# host-Insulation.net
KiCad netlist of a schematic drawn in EAGLE
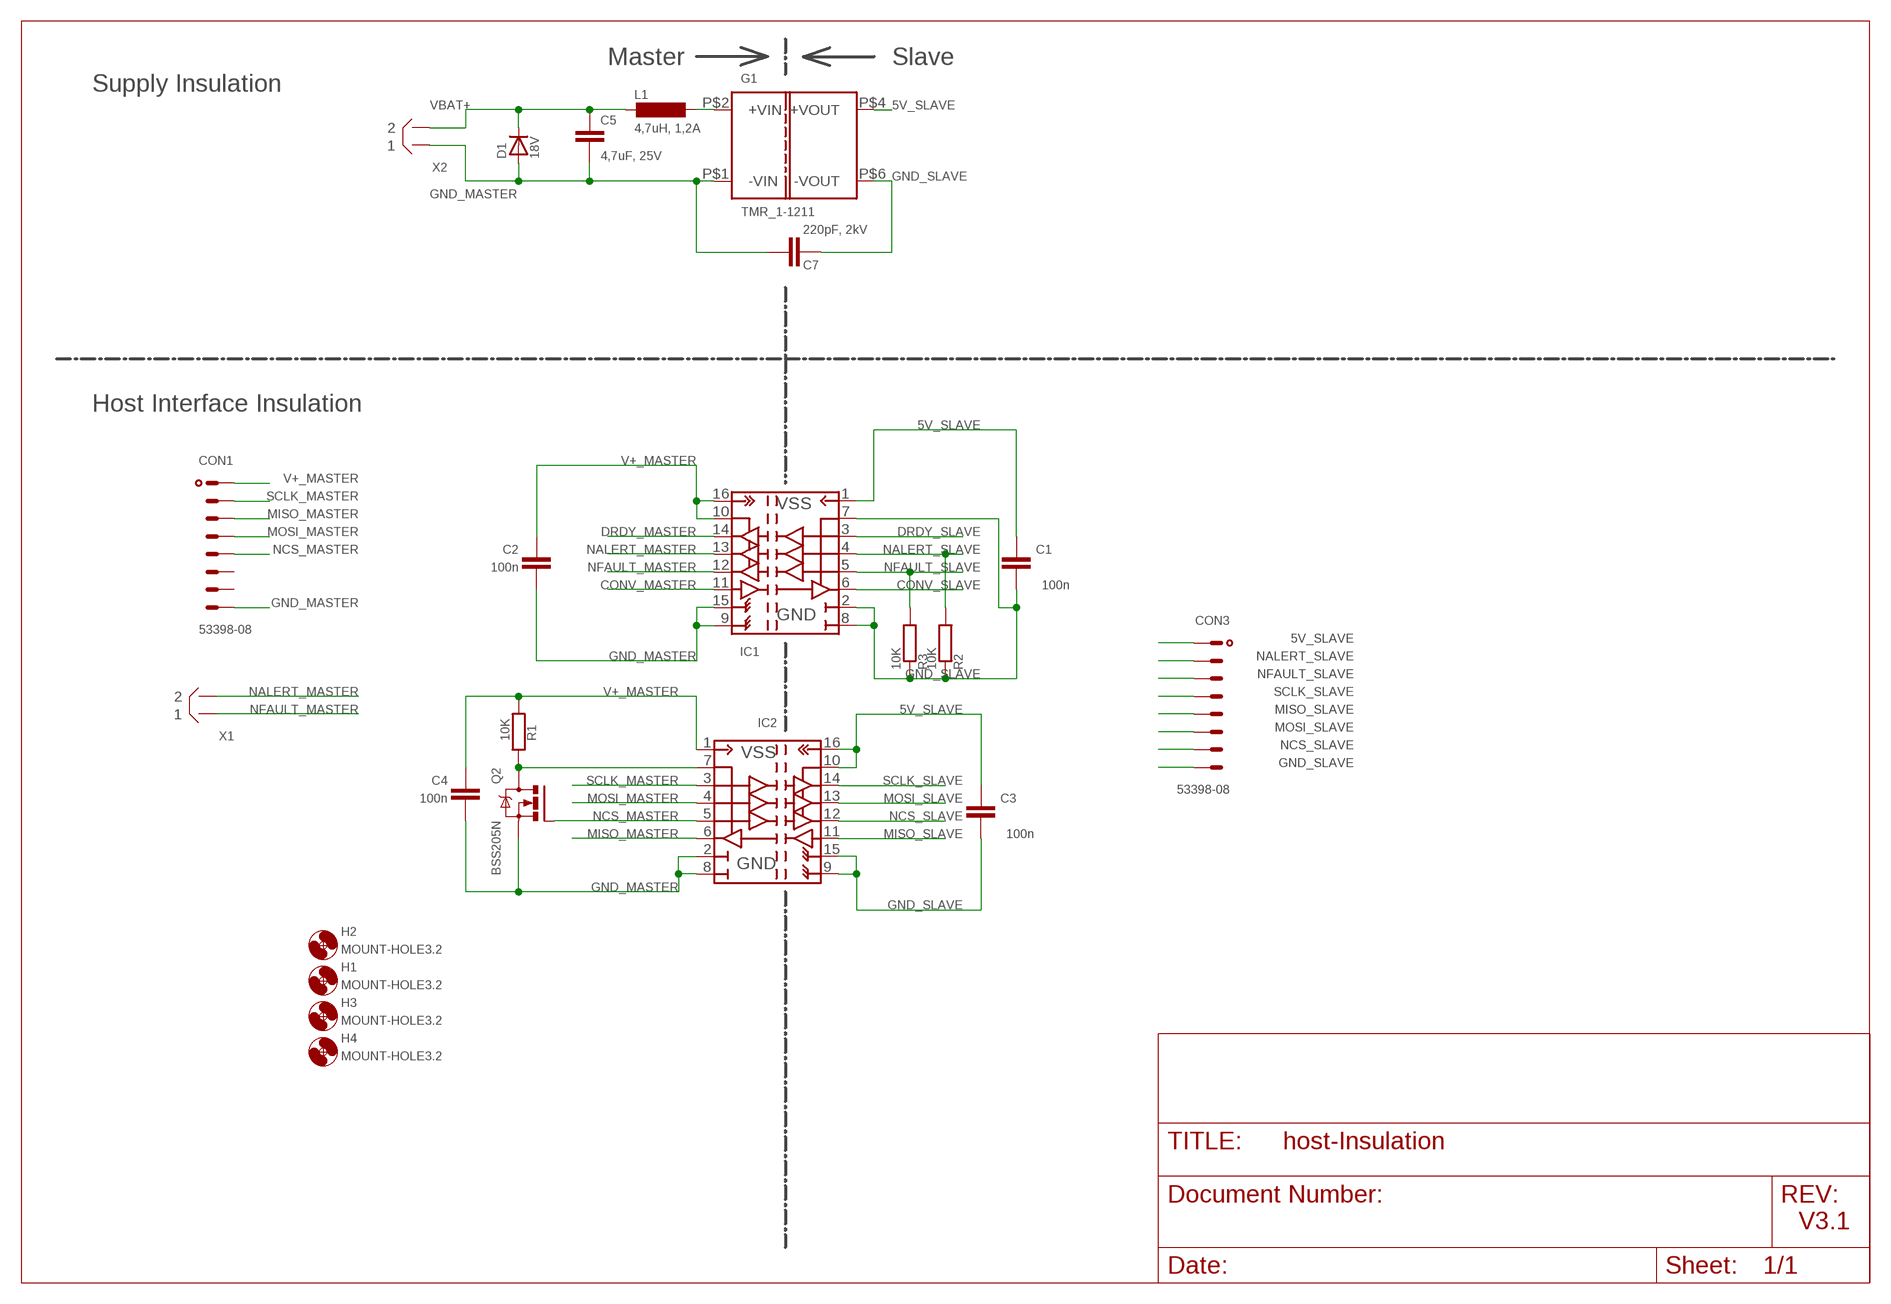
[diagram p0: schematic, sheet 1]

(export (version "E")
  (design (tool "Eeschema 10.0.6"))
  (components
    (comp (ref "C1")
      (value "100n")
      (footprint "eagle-import:C0805")
      (libsource (lib "eagle-import") (part "CSTD"))
    )
    (comp (ref "C2")
      (value "100n")
      (footprint "eagle-import:C0805")
      (libsource (lib "eagle-import") (part "CSTD"))
    )
    (comp (ref "C3")
      (value "100n")
      (footprint "eagle-import:C0805")
      (libsource (lib "eagle-import") (part "CSTD"))
    )
    (comp (ref "C4")
      (value "100n")
      (footprint "eagle-import:C0805")
      (libsource (lib "eagle-import") (part "CSTD"))
    )
    (comp (ref "C5")
      (value "4,7uF, 25V")
      (footprint "eagle-import:C0805")
      (libsource (lib "eagle-import") (part "C-EUC0805"))
    )
    (comp (ref "C7")
      (value "220pF, 2kV")
      (footprint "eagle-import:C1210_HV")
      (libsource (lib "eagle-import") (part "CC1210_HV"))
    )
    (comp (ref "CON1")
      (value "53398-08")
      (footprint "eagle-import:53398-08")
      (libsource (lib "eagle-import") (part "53?-08398"))
    )
    (comp (ref "CON3")
      (value "53398-08")
      (footprint "eagle-import:53398-08")
      (libsource (lib "eagle-import") (part "53?-08398"))
    )
    (comp (ref "D1")
      (value "18V")
      (footprint "eagle-import:DO214AA")
      (libsource (lib "eagle-import") (part "DIODE-DO214AA"))
    )
    (comp (ref "G1")
      (value "TMR_1-1211")
      (footprint "eagle-import:TMR_1-__1_")
      (libsource (lib "eagle-import") (part "TMR_1-??1?"))
    )
    (comp (ref "H1")
      (value "MOUNT-HOLE3.2")
      (footprint "eagle-import:3,2")
      (libsource (lib "eagle-import") (part "MOUNT-HOLE3.2"))
    )
    (comp (ref "H2")
      (value "MOUNT-HOLE3.2")
      (footprint "eagle-import:3,2")
      (libsource (lib "eagle-import") (part "MOUNT-HOLE3.2"))
    )
    (comp (ref "H3")
      (value "MOUNT-HOLE3.2")
      (footprint "eagle-import:3,2")
      (libsource (lib "eagle-import") (part "MOUNT-HOLE3.2"))
    )
    (comp (ref "H4")
      (value "MOUNT-HOLE3.2")
      (footprint "eagle-import:3,2")
      (libsource (lib "eagle-import") (part "MOUNT-HOLE3.2"))
    )
    (comp (ref "IC1")
      (value "ISO7241")
      (footprint "eagle-import:R-PDSO-G16")
      (libsource (lib "eagle-import") (part "ISO7241"))
    )
    (comp (ref "IC2")
      (value "ISO7241")
      (footprint "eagle-import:R-PDSO-G16")
      (libsource (lib "eagle-import") (part "ISO7241"))
    )
    (comp (ref "L1")
      (value "4,7uH, 1,2A")
      (footprint "eagle-import:L3225M")
      (libsource (lib "eagle-import") (part "L-EUL3225M"))
    )
    (comp (ref "Q2")
      (value "BSS205N")
      (footprint "eagle-import:SOT23")
      (libsource (lib "eagle-import") (part "BSS205N"))
    )
    (comp (ref "R1")
      (value "10K")
      (footprint "eagle-import:R0805")
      (libsource (lib "eagle-import") (part "R"))
    )
    (comp (ref "R2")
      (value "10K")
      (footprint "eagle-import:R0805")
      (libsource (lib "eagle-import") (part "R"))
    )
    (comp (ref "R3")
      (value "10K")
      (footprint "eagle-import:R0805")
      (libsource (lib "eagle-import") (part "R"))
    )
    (comp (ref "X1")
      (value "B2B-XH")
      (footprint "eagle-import:B2B-XH")
      (libsource (lib "eagle-import") (part "?2B-XHB"))
    )
    (comp (ref "X2")
      (value "B2B-XH")
      (footprint "eagle-import:B2B-XH")
      (libsource (lib "eagle-import") (part "?2B-XHB"))
    )
  )
  (nets
    (net (code "1") (name "/5V_SLAVE") (class "Default")
      (node (ref "C1") (pin "2") (pinfunction "2_2") (pintype "passive"))
      (node (ref "C3") (pin "2") (pinfunction "2_2") (pintype "passive"))
      (node (ref "CON3") (pin "1") (pinfunction "1_1") (pintype "passive"))
      (node (ref "G1") (pin "P$4") (pinfunction "+VOUT_P$4") (pintype "bidirectional"))
      (node (ref "IC1") (pin "1") (pinfunction "VCC1_1") (pintype "bidirectional"))
      (node (ref "IC2") (pin "10") (pinfunction "EN2_10") (pintype "bidirectional"))
      (node (ref "IC2") (pin "16") (pinfunction "VCC2_16") (pintype "bidirectional"))
    )
    (net (code "2") (name "/CONV_MASTER") (class "Default")
      (node (ref "IC1") (pin "11") (pinfunction "IN_D_11") (pintype "bidirectional"))
    )
    (net (code "3") (name "/CONV_SLAVE") (class "Default")
      (node (ref "IC1") (pin "6") (pinfunction "OUT_D_6") (pintype "bidirectional"))
    )
    (net (code "4") (name "/DRDY_MASTER") (class "Default")
      (node (ref "IC1") (pin "14") (pinfunction "OUT_A_14") (pintype "bidirectional"))
    )
    (net (code "5") (name "/DRDY_SLAVE") (class "Default")
      (node (ref "IC1") (pin "3") (pinfunction "IN_A_3") (pintype "bidirectional"))
    )
    (net (code "6") (name "/GND_MASTER") (class "Default")
      (node (ref "C2") (pin "1") (pinfunction "1_1") (pintype "passive"))
      (node (ref "C4") (pin "1") (pinfunction "1_1") (pintype "passive"))
      (node (ref "C5") (pin "2") (pinfunction "2_2") (pintype "passive"))
      (node (ref "C7") (pin "P$1") (pinfunction "1_P$1") (pintype "passive"))
      (node (ref "CON1") (pin "8") (pinfunction "8_8") (pintype "passive"))
      (node (ref "D1") (pin "A") (pinfunction "A_A") (pintype "passive"))
      (node (ref "G1") (pin "P$1") (pinfunction "-VIN_P$1") (pintype "bidirectional"))
      (node (ref "IC1") (pin "15") (pinfunction "GND21_15") (pintype "bidirectional"))
      (node (ref "IC1") (pin "9") (pinfunction "GND22_9") (pintype "bidirectional"))
      (node (ref "IC2") (pin "2") (pinfunction "GND11_2") (pintype "bidirectional"))
      (node (ref "IC2") (pin "8") (pinfunction "GND12_8") (pintype "bidirectional"))
      (node (ref "Q2") (pin "2") (pinfunction "S_2") (pintype "passive"))
      (node (ref "X2") (pin "P$1") (pinfunction "1_P$1") (pintype "bidirectional"))
    )
    (net (code "7") (name "/GND_SLAVE") (class "Default")
      (node (ref "C1") (pin "1") (pinfunction "1_1") (pintype "passive"))
      (node (ref "C3") (pin "1") (pinfunction "1_1") (pintype "passive"))
      (node (ref "C7") (pin "P$2") (pinfunction "2_P$2") (pintype "passive"))
      (node (ref "CON3") (pin "8") (pinfunction "8_8") (pintype "passive"))
      (node (ref "G1") (pin "P$6") (pinfunction "-VOUT_P$6") (pintype "bidirectional"))
      (node (ref "IC1") (pin "2") (pinfunction "GND11_2") (pintype "bidirectional"))
      (node (ref "IC1") (pin "7") (pinfunction "EN1_7") (pintype "bidirectional"))
      (node (ref "IC1") (pin "8") (pinfunction "GND12_8") (pintype "bidirectional"))
      (node (ref "IC2") (pin "15") (pinfunction "GND21_15") (pintype "bidirectional"))
      (node (ref "IC2") (pin "9") (pinfunction "GND22_9") (pintype "bidirectional"))
      (node (ref "R2") (pin "1") (pinfunction "1_1") (pintype "passive"))
      (node (ref "R3") (pin "1") (pinfunction "1_1") (pintype "passive"))
    )
    (net (code "8") (name "/MISO_MASTER") (class "Default")
      (node (ref "CON1") (pin "3") (pinfunction "3_3") (pintype "passive"))
      (node (ref "IC2") (pin "6") (pinfunction "OUT_D_6") (pintype "bidirectional"))
    )
    (net (code "9") (name "/MISO_SLAVE") (class "Default")
      (node (ref "CON3") (pin "5") (pinfunction "5_5") (pintype "passive"))
      (node (ref "IC2") (pin "11") (pinfunction "IN_D_11") (pintype "bidirectional"))
    )
    (net (code "10") (name "/MOSI_MASTER") (class "Default")
      (node (ref "CON1") (pin "4") (pinfunction "4_4") (pintype "passive"))
      (node (ref "IC2") (pin "4") (pinfunction "IN_B_4") (pintype "bidirectional"))
    )
    (net (code "11") (name "/MOSI_SLAVE") (class "Default")
      (node (ref "CON3") (pin "6") (pinfunction "6_6") (pintype "passive"))
      (node (ref "IC2") (pin "13") (pinfunction "OUT_B_13") (pintype "bidirectional"))
    )
    (net (code "12") (name "/NALERT_MASTER") (class "Default")
      (node (ref "IC1") (pin "13") (pinfunction "OUT_B_13") (pintype "bidirectional"))
      (node (ref "X1") (pin "P$2") (pinfunction "2_P$2") (pintype "bidirectional"))
    )
    (net (code "13") (name "/NALERT_SLAVE") (class "Default")
      (node (ref "CON3") (pin "2") (pinfunction "2_2") (pintype "passive"))
      (node (ref "IC1") (pin "4") (pinfunction "IN_B_4") (pintype "bidirectional"))
      (node (ref "R2") (pin "2") (pinfunction "2_2") (pintype "passive"))
    )
    (net (code "14") (name "/NCS_MASTER") (class "Default")
      (node (ref "CON1") (pin "5") (pinfunction "5_5") (pintype "passive"))
      (node (ref "IC2") (pin "5") (pinfunction "IN_C_5") (pintype "bidirectional"))
      (node (ref "Q2") (pin "1") (pinfunction "G_1") (pintype "passive"))
    )
    (net (code "15") (name "/NCS_SLAVE") (class "Default")
      (node (ref "CON3") (pin "7") (pinfunction "7_7") (pintype "passive"))
      (node (ref "IC2") (pin "12") (pinfunction "OUT_C_12") (pintype "bidirectional"))
    )
    (net (code "16") (name "/NFAULT_MASTER") (class "Default")
      (node (ref "IC1") (pin "12") (pinfunction "OUT_C_12") (pintype "bidirectional"))
      (node (ref "X1") (pin "P$1") (pinfunction "1_P$1") (pintype "bidirectional"))
    )
    (net (code "17") (name "/NFAULT_SLAVE") (class "Default")
      (node (ref "CON3") (pin "3") (pinfunction "3_3") (pintype "passive"))
      (node (ref "IC1") (pin "5") (pinfunction "IN_C_5") (pintype "bidirectional"))
      (node (ref "R3") (pin "2") (pinfunction "2_2") (pintype "passive"))
    )
    (net (code "18") (name "/SCLK_MASTER") (class "Default")
      (node (ref "CON1") (pin "2") (pinfunction "2_2") (pintype "passive"))
      (node (ref "IC2") (pin "3") (pinfunction "IN_A_3") (pintype "bidirectional"))
    )
    (net (code "19") (name "/SCLK_SLAVE") (class "Default")
      (node (ref "CON3") (pin "4") (pinfunction "4_4") (pintype "passive"))
      (node (ref "IC2") (pin "14") (pinfunction "OUT_A_14") (pintype "bidirectional"))
    )
    (net (code "20") (name "/V+_MASTER") (class "Default")
      (node (ref "C2") (pin "2") (pinfunction "2_2") (pintype "passive"))
      (node (ref "C4") (pin "2") (pinfunction "2_2") (pintype "passive"))
      (node (ref "CON1") (pin "1") (pinfunction "1_1") (pintype "passive"))
      (node (ref "IC1") (pin "10") (pinfunction "EN2_10") (pintype "bidirectional"))
      (node (ref "IC1") (pin "16") (pinfunction "VCC2_16") (pintype "bidirectional"))
      (node (ref "IC2") (pin "1") (pinfunction "VCC1_1") (pintype "bidirectional"))
      (node (ref "R1") (pin "2") (pinfunction "2_2") (pintype "passive"))
    )
    (net (code "21") (name "/VBAT+") (class "Default")
      (node (ref "C5") (pin "1") (pinfunction "1_1") (pintype "passive"))
      (node (ref "D1") (pin "C") (pinfunction "C_C") (pintype "passive"))
      (node (ref "L1") (pin "2") (pinfunction "2_2") (pintype "passive"))
      (node (ref "X2") (pin "P$2") (pinfunction "2_P$2") (pintype "bidirectional"))
    )
    (net (code "22") (name "Net-(G1-+VIN)") (class "Default")
      (node (ref "G1") (pin "P$2") (pinfunction "+VIN_P$2") (pintype "bidirectional"))
      (node (ref "L1") (pin "1") (pinfunction "1_1") (pintype "passive"))
    )
    (net (code "23") (name "Net-(IC2-EN1)") (class "Default")
      (node (ref "IC2") (pin "7") (pinfunction "EN1_7") (pintype "bidirectional"))
      (node (ref "Q2") (pin "3") (pinfunction "D_3") (pintype "passive"))
      (node (ref "R1") (pin "1") (pinfunction "1_1") (pintype "passive"))
    )
    (net (code "24") (name "unconnected-(CON1-Pad6)") (class "Default")
      (node (ref "CON1") (pin "6") (pinfunction "6_6") (pintype "passive"))
    )
    (net (code "25") (name "unconnected-(CON1-Pad7)") (class "Default")
      (node (ref "CON1") (pin "7") (pinfunction "7_7") (pintype "passive"))
    )
  )
)
